# Port.net
KiCad netlist of a schematic drawn in Altium Designer
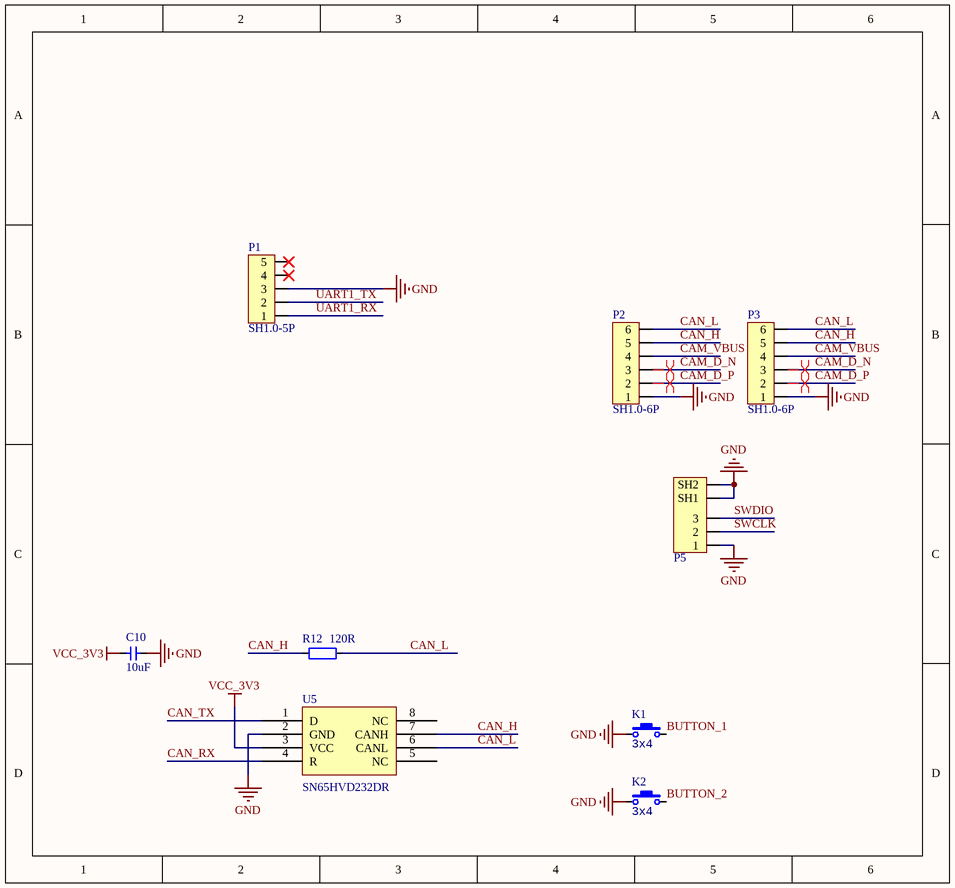
[diagram p0: Port.SchDoc]

(export (version "E")
  (design (tool "Eeschema 10.0.6"))
  (components
    (comp (ref "C10")
      (value "10uF")
      (footprint "CAP_0402")
      (description "Capacitor")
      (libsource (lib "MyPcbLib") (part "电容-0402"))
    )
    (comp (ref "K1")
      (value "3x4")
      (footprint "ButtonTACT_3x4x2_180")
      (description "Button")
      (fields (field (name "Comment") "TACT 2P"))
      (libsource (lib "KitSprout") (part "ButtonTACT_3x4x2_180"))
    )
    (comp (ref "K2")
      (value "3x4")
      (footprint "ButtonTACT_3x4x2_180")
      (description "Button")
      (fields (field (name "Comment") "TACT 2P"))
      (libsource (lib "KitSprout") (part "ButtonTACT_3x4x2_180"))
    )
    (comp (ref "P1") (value "SH1.0-5P") (footprint "SH1.0-5P") (libsource (lib "MyPcbLib") (part "SH1.0-5P")))
    (comp (ref "P2") (value "SH1.0-6P") (footprint "SH1.0-6P") (libsource (lib "MyPcbLib") (part "SH1.0-6P")))
    (comp (ref "P3") (value "SH1.0-6P") (footprint "SH1.0-6P") (libsource (lib "MyPcbLib") (part "SH1.0-6P")))
    (comp (ref "P5")
      (value "SH1.0-3P")
      (footprint "SH1.0-3P")
      (description "Header")
      (libsource (lib "MyPcbLib") (part "SH1.0-3P"))
    )
    (comp (ref "R12")
      (value "120R")
      (footprint "RES_0402")
      (description "Resistor")
      (libsource (lib "MyPcbLib") (part "电阻-0402"))
    )
    (comp (ref "U5")
      (value "SN65HVD232D")
      (footprint "SO-8")
      (fields
        (field (name "MANUFACTURER") "Texas Instruments")
        (field (name "MANUFACTURER PART NUMBER") "SN65HVD232DR")
      )
      (libsource (lib "MyPcbLib") (part "SN65HVD232D"))
    )
  )
  (nets
    (net (code "1") (name "/BUTTON_1") (class "Default")
      (node (ref "K1") (pin "2") (pinfunction "2_2") (pintype "passive"))
    )
    (net (code "2") (name "/BUTTON_2") (class "Default")
      (node (ref "K2") (pin "2") (pinfunction "2_2") (pintype "passive"))
    )
    (net (code "3") (name "/CAM_D_N") (class "Default")
      (node (ref "P2") (pin "3") (pinfunction "3_3") (pintype "passive"))
      (node (ref "P3") (pin "3") (pinfunction "3_3") (pintype "passive"))
    )
    (net (code "4") (name "/CAM_D_P") (class "Default")
      (node (ref "P2") (pin "2") (pinfunction "2_2") (pintype "passive"))
      (node (ref "P3") (pin "2") (pinfunction "2_2") (pintype "passive"))
    )
    (net (code "5") (name "/CAM_VBUS") (class "Default")
      (node (ref "P2") (pin "4") (pinfunction "4_4") (pintype "passive"))
      (node (ref "P3") (pin "4") (pinfunction "4_4") (pintype "passive"))
    )
    (net (code "6") (name "/CAN_H") (class "Default")
      (node (ref "P2") (pin "5") (pinfunction "5_5") (pintype "passive"))
      (node (ref "P3") (pin "5") (pinfunction "5_5") (pintype "passive"))
      (node (ref "R12") (pin "1") (pinfunction "1_1") (pintype "passive"))
      (node (ref "U5") (pin "7") (pinfunction "CANH_7") (pintype "passive"))
    )
    (net (code "7") (name "/CAN_L") (class "Default")
      (node (ref "P2") (pin "6") (pinfunction "6_6") (pintype "passive"))
      (node (ref "P3") (pin "6") (pinfunction "6_6") (pintype "passive"))
      (node (ref "R12") (pin "2") (pinfunction "2_2") (pintype "passive"))
      (node (ref "U5") (pin "6") (pinfunction "CANL_6") (pintype "passive"))
    )
    (net (code "8") (name "/CAN_RX") (class "Default")
      (node (ref "U5") (pin "4") (pinfunction "R_4") (pintype "passive"))
    )
    (net (code "9") (name "/CAN_TX") (class "Default")
      (node (ref "U5") (pin "1") (pinfunction "D_1") (pintype "passive"))
    )
    (net (code "10") (name "/SWCLK") (class "Default")
      (node (ref "P5") (pin "2") (pinfunction "2_2") (pintype "passive"))
    )
    (net (code "11") (name "/SWDIO") (class "Default")
      (node (ref "P5") (pin "3") (pinfunction "3_3") (pintype "passive"))
    )
    (net (code "12") (name "/UART1_RX") (class "Default")
      (node (ref "P1") (pin "1") (pinfunction "1_1") (pintype "passive"))
    )
    (net (code "13") (name "/UART1_TX") (class "Default")
      (node (ref "P1") (pin "2") (pinfunction "2_2") (pintype "passive"))
    )
    (net (code "14") (name "GND") (class "Default")
      (node (ref "C10") (pin "1") (pinfunction "1_1") (pintype "passive"))
      (node (ref "K1") (pin "1") (pinfunction "1_1") (pintype "passive"))
      (node (ref "K2") (pin "1") (pinfunction "1_1") (pintype "passive"))
      (node (ref "P1") (pin "3") (pinfunction "3_3") (pintype "passive"))
      (node (ref "P2") (pin "1") (pinfunction "1_1") (pintype "passive"))
      (node (ref "P3") (pin "1") (pinfunction "1_1") (pintype "passive"))
      (node (ref "P5") (pin "1") (pinfunction "1_1") (pintype "passive"))
      (node (ref "P5") (pin "SH1") (pinfunction "SH1_SH1") (pintype "passive"))
      (node (ref "P5") (pin "SH2") (pinfunction "SH2_SH2") (pintype "passive"))
      (node (ref "U5") (pin "2") (pinfunction "GND_2") (pintype "passive"))
    )
    (net (code "15") (name "VCC_3V3") (class "Default")
      (node (ref "C10") (pin "2") (pinfunction "2_2") (pintype "passive"))
      (node (ref "U5") (pin "3") (pinfunction "VCC_3") (pintype "passive"))
    )
    (net (code "16") (name "unconnected-(P1-Pad4)") (class "Default")
      (node (ref "P1") (pin "4") (pinfunction "4_4") (pintype "passive+no_connect"))
    )
    (net (code "17") (name "unconnected-(P1-Pad5)") (class "Default")
      (node (ref "P1") (pin "5") (pinfunction "5_5") (pintype "passive+no_connect"))
    )
    (net (code "18") (name "unconnected-(U5-NC-Pad5)") (class "Default")
      (node (ref "U5") (pin "5") (pinfunction "NC_5") (pintype "passive"))
    )
    (net (code "19") (name "unconnected-(U5-NC-Pad8)") (class "Default")
      (node (ref "U5") (pin "8") (pinfunction "NC_8") (pintype "passive"))
    )
  )
)
